# PPMB32-F.net
KiCad netlist of a schematic drawn in EAGLE
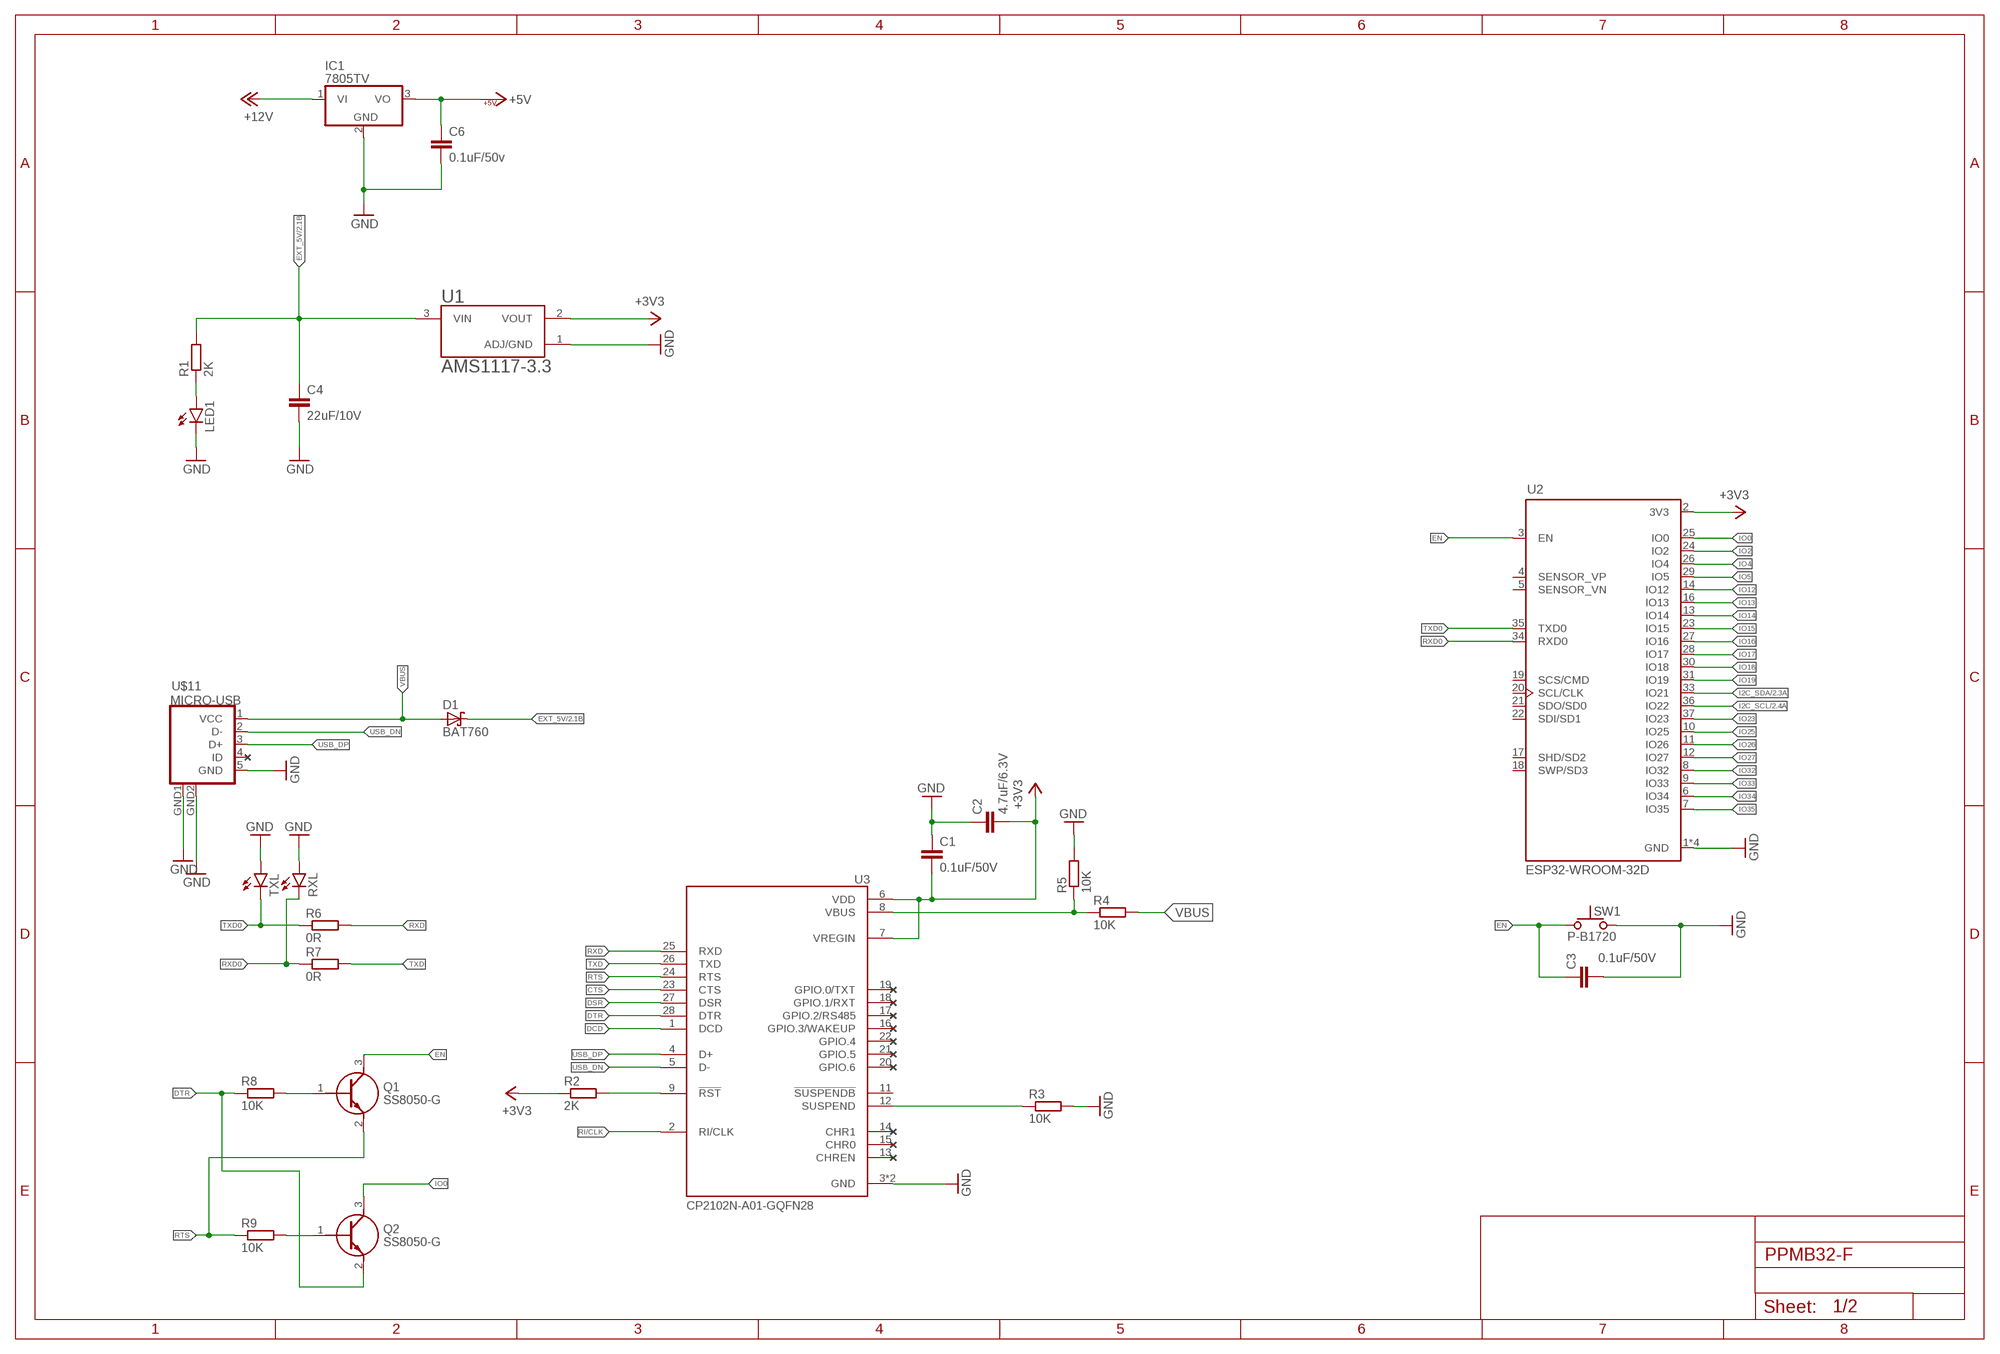
[diagram p0: schematic, sheet 1]
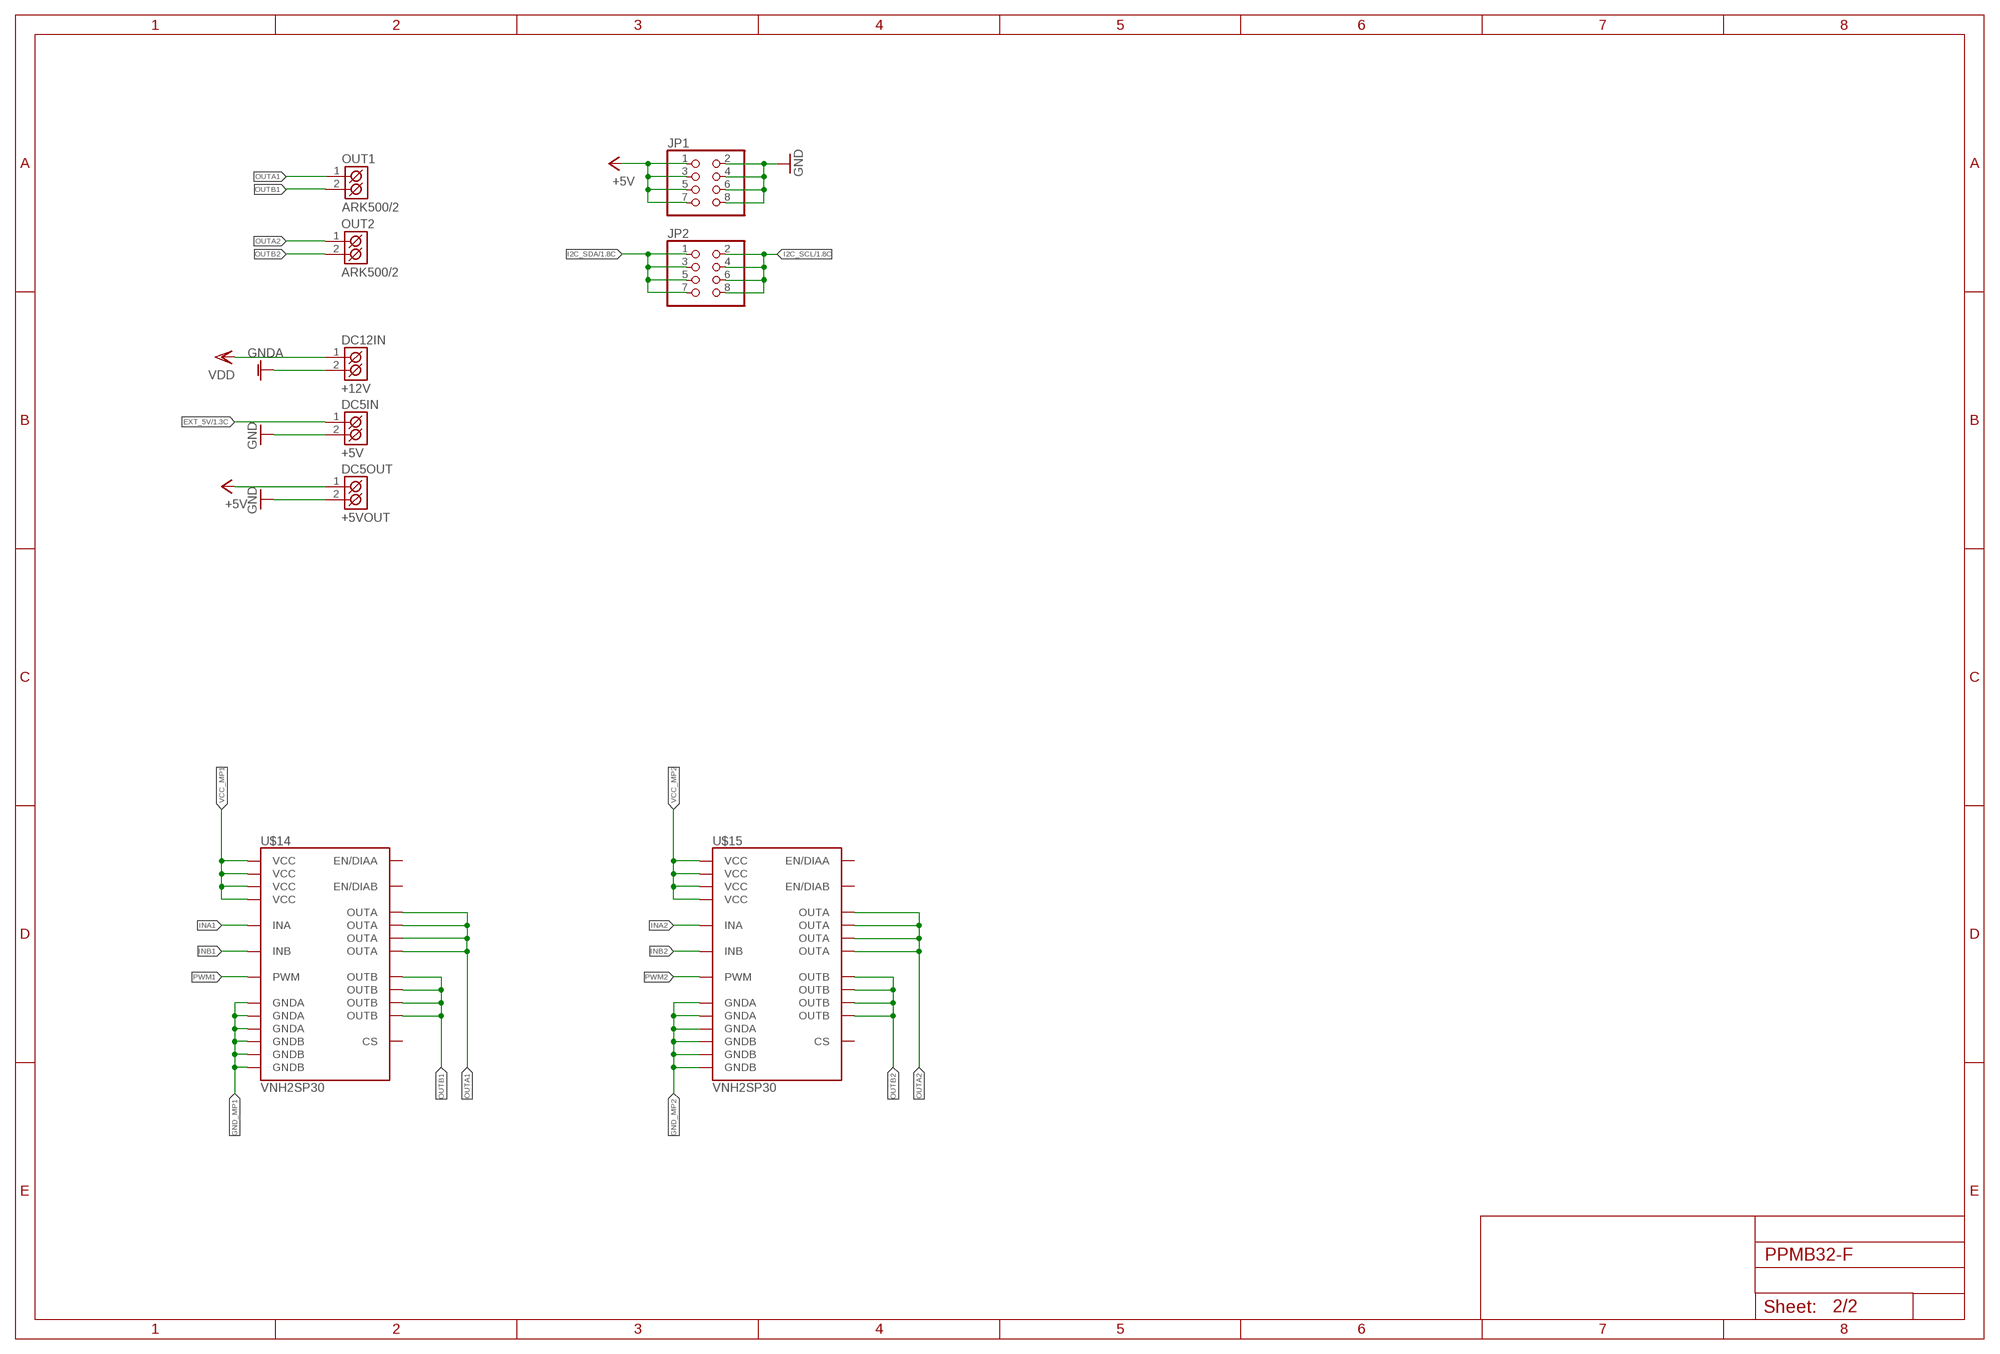
[diagram p1: schematic, sheet 2]

(export (version "E")
  (design (tool "Eeschema 10.0.6"))
  (components
    (comp (ref "C1")
      (value "0.1uF/50V")
      (footprint "eagle-import:C0603")
      (libsource (lib "eagle-import") (part "C-EUC0603"))
    )
    (comp (ref "C2")
      (value "4.7uF/6.3V")
      (footprint "eagle-import:C0603")
      (libsource (lib "eagle-import") (part "C-EUC0603"))
    )
    (comp (ref "C3")
      (value "0.1uF/50V")
      (footprint "eagle-import:C0603")
      (libsource (lib "eagle-import") (part "C-EUC0603"))
    )
    (comp (ref "C4")
      (value "22uF/10V")
      (footprint "eagle-import:C0603")
      (libsource (lib "eagle-import") (part "C-EUC0603"))
    )
    (comp (ref "C6")
      (value "0.1uF/50v")
      (footprint "eagle-import:C0603")
      (libsource (lib "eagle-import") (part "C-EUC0603"))
    )
    (comp (ref "D1")
      (value "BAT760")
      (footprint "eagle-import:SOD323(F)")
      (libsource (lib "eagle-import") (part "BAT760"))
    )
    (comp (ref "IC1")
      (value "7805TV")
      (footprint "eagle-import:TO220V")
      (libsource (lib "eagle-import") (part "78TV05"))
    )
    (comp (ref "LED1")
      (value "LEDCHIP-LED0603")
      (footprint "eagle-import:CHIP-LED0603")
      (libsource (lib "eagle-import") (part "LEDCHIP-LED0603"))
    )
    (comp (ref "Q1")
      (value "SS8050-G")
      (footprint "eagle-import:SOT95P240X115-3N")
      (fields (field (name "MF") "Comchip Technology"))
      (libsource (lib "eagle-import") (part "SS8050-G"))
    )
    (comp (ref "Q2")
      (value "SS8050-G")
      (footprint "eagle-import:SOT95P240X115-3N")
      (fields (field (name "MF") "Comchip Technology"))
      (libsource (lib "eagle-import") (part "SS8050-G"))
    )
    (comp (ref "R1")
      (value "2K")
      (footprint "eagle-import:R0603")
      (libsource (lib "eagle-import") (part "R-EU_R0603"))
    )
    (comp (ref "R2")
      (value "2K")
      (footprint "eagle-import:R0603")
      (libsource (lib "eagle-import") (part "R-EU_R0603"))
    )
    (comp (ref "R3")
      (value "10K")
      (footprint "eagle-import:R0603")
      (libsource (lib "eagle-import") (part "R-EU_R0603"))
    )
    (comp (ref "R4")
      (value "10K")
      (footprint "eagle-import:R0603")
      (libsource (lib "eagle-import") (part "R-EU_R0603"))
    )
    (comp (ref "R5")
      (value "10K")
      (footprint "eagle-import:R0603")
      (libsource (lib "eagle-import") (part "R-EU_R0603"))
    )
    (comp (ref "R6")
      (value "0R")
      (footprint "eagle-import:R0603")
      (libsource (lib "eagle-import") (part "R-EU_R0603"))
    )
    (comp (ref "R7")
      (value "0R")
      (footprint "eagle-import:R0603")
      (libsource (lib "eagle-import") (part "R-EU_R0603"))
    )
    (comp (ref "R8")
      (value "10K")
      (footprint "eagle-import:R0603")
      (libsource (lib "eagle-import") (part "R-EU_R0603"))
    )
    (comp (ref "R9")
      (value "10K")
      (footprint "eagle-import:R0603")
      (libsource (lib "eagle-import") (part "R-EU_R0603"))
    )
    (comp (ref "RXL")
      (value "LEDCHIP-LED0603")
      (footprint "eagle-import:CHIP-LED0603")
      (libsource (lib "eagle-import") (part "LEDCHIP-LED0603"))
    )
    (comp (ref "SW1")
      (value "P-B1720")
      (footprint "eagle-import:P-B1720")
      (libsource (lib "eagle-import") (part "P-B1720"))
    )
    (comp (ref "TXL")
      (value "LEDCHIP-LED0603")
      (footprint "eagle-import:CHIP-LED0603")
      (libsource (lib "eagle-import") (part "LEDCHIP-LED0603"))
    )
    (comp (ref "U$11")
      (value "MICRO-USB")
      (footprint "eagle-import:MICRO-USB")
      (libsource (lib "eagle-import") (part "MICRO-USB"))
    )
    (comp (ref "U1")
      (value "AMS1117-3.3")
      (footprint "eagle-import:SOT229P700X180-4N")
      (fields (field (name "MF") "Advanced Monolithic Systems"))
      (libsource (lib "eagle-import") (part "AMS1117-3.3"))
    )
    (comp (ref "U2")
      (value "ESP32-WROOM-32D")
      (footprint "eagle-import:MODULE_ESP32-WROOM-32D")
      (fields (field (name "MF") "Espressif Systems"))
      (libsource (lib "eagle-import") (part "ESP32-WROOM-32D"))
    )
    (comp (ref "U3")
      (value "CP2102N-A01-GQFN28")
      (footprint "eagle-import:QFN50P500X500X80-29N")
      (fields (field (name "MF") "Silicon Labs"))
      (libsource (lib "eagle-import") (part "CP2102N-A01-GQFN28"))
    )
    (comp (ref "DC5IN")
      (value "+5V")
      (footprint "eagle-import:ARK500_2")
      (libsource (lib "eagle-import") (part "ARK500/2"))
    )
    (comp (ref "DC5OUT")
      (value "+5VOUT")
      (footprint "eagle-import:ARK500_2")
      (libsource (lib "eagle-import") (part "ARK500/2"))
    )
    (comp (ref "DC12IN")
      (value "+12V")
      (footprint "eagle-import:ARK500_2")
      (libsource (lib "eagle-import") (part "ARK500/2"))
    )
    (comp (ref "JP1")
      (value "PINHD-2X4")
      (footprint "eagle-import:2X04")
      (libsource (lib "eagle-import") (part "PINHD-2X4"))
    )
    (comp (ref "JP2")
      (value "PINHD-2X4")
      (footprint "eagle-import:2X04")
      (libsource (lib "eagle-import") (part "PINHD-2X4"))
    )
    (comp (ref "OUT1")
      (value "ARK500/2")
      (footprint "eagle-import:ARK500_2")
      (libsource (lib "eagle-import") (part "ARK500/2"))
    )
    (comp (ref "OUT2")
      (value "ARK500/2")
      (footprint "eagle-import:ARK500_2")
      (libsource (lib "eagle-import") (part "ARK500/2"))
    )
    (comp (ref "U$14")
      (value "VNH2SP30")
      (footprint "eagle-import:VNH2SP30")
      (libsource (lib "eagle-import") (part "VNH2SP30"))
    )
    (comp (ref "U$15")
      (value "VNH2SP30")
      (footprint "eagle-import:VNH2SP30")
      (libsource (lib "eagle-import") (part "VNH2SP30"))
    )
  )
  (nets
    (net (code "1") (name "+3V3") (class "Default")
      (node (ref "C1") (pin "2") (pinfunction "2_2") (pintype "passive"))
      (node (ref "C2") (pin "2") (pinfunction "2_2") (pintype "passive"))
      (node (ref "R2") (pin "1") (pinfunction "1_1") (pintype "passive"))
      (node (ref "U1") (pin "2") (pinfunction "VOUT_2") (pintype "output"))
      (node (ref "U2") (pin "2") (pinfunction "3V3_2") (pintype "power_in"))
      (node (ref "U3") (pin "6") (pinfunction "VDD_6") (pintype "power_in"))
      (node (ref "U3") (pin "7") (pinfunction "VREGIN_7") (pintype "power_in"))
    )
    (net (code "2") (name "+5V") (class "Default")
      (node (ref "C6") (pin "1") (pinfunction "1_1") (pintype "passive"))
      (node (ref "DC5OUT") (pin "1") (pinfunction "K1_1") (pintype "passive"))
      (node (ref "IC1") (pin "3") (pinfunction "VO_3") (pintype "passive"))
      (node (ref "JP1") (pin "1") (pinfunction "1_1") (pintype "passive"))
      (node (ref "JP1") (pin "3") (pinfunction "3_3") (pintype "passive"))
      (node (ref "JP1") (pin "5") (pinfunction "5_5") (pintype "passive"))
      (node (ref "JP1") (pin "7") (pinfunction "7_7") (pintype "passive"))
    )
    (net (code "3") (name "+12V") (class "Default")
      (node (ref "IC1") (pin "1") (pinfunction "VI_1") (pintype "input"))
    )
    (net (code "4") (name "CTS") (class "Default")
      (node (ref "U3") (pin "23") (pinfunction "CTS_23") (pintype "input"))
    )
    (net (code "5") (name "DCD") (class "Default")
      (node (ref "U3") (pin "1") (pinfunction "DCD_1") (pintype "input"))
    )
    (net (code "6") (name "DSR") (class "Default")
      (node (ref "U3") (pin "27") (pinfunction "DSR_27") (pintype "input"))
    )
    (net (code "7") (name "DTR") (class "Default")
      (node (ref "Q2") (pin "2") (pinfunction "E_2") (pintype "bidirectional"))
      (node (ref "R8") (pin "1") (pinfunction "1_1") (pintype "passive"))
      (node (ref "U3") (pin "28") (pinfunction "DTR_28") (pintype "output"))
    )
    (net (code "8") (name "EN") (class "Default")
      (node (ref "C3") (pin "1") (pinfunction "1_1") (pintype "passive"))
      (node (ref "Q1") (pin "3") (pinfunction "C_3") (pintype "bidirectional"))
      (node (ref "SW1") (pin "1") (pinfunction "1_1") (pintype "passive"))
      (node (ref "U2") (pin "3") (pinfunction "EN_3") (pintype "input"))
    )
    (net (code "9") (name "EXT_5V") (class "Default")
      (node (ref "C4") (pin "1") (pinfunction "1_1") (pintype "passive"))
      (node (ref "D1") (pin "1") (pinfunction "K_1") (pintype "passive"))
      (node (ref "DC5IN") (pin "1") (pinfunction "K1_1") (pintype "passive"))
      (node (ref "R1") (pin "2") (pinfunction "2_2") (pintype "passive"))
      (node (ref "U1") (pin "3") (pinfunction "VIN_3") (pintype "input"))
    )
    (net (code "10") (name "GND") (class "Default")
      (node (ref "C1") (pin "1") (pinfunction "1_1") (pintype "passive"))
      (node (ref "C2") (pin "1") (pinfunction "1_1") (pintype "passive"))
      (node (ref "C3") (pin "2") (pinfunction "2_2") (pintype "passive"))
      (node (ref "C4") (pin "2") (pinfunction "2_2") (pintype "passive"))
      (node (ref "C6") (pin "2") (pinfunction "2_2") (pintype "passive"))
      (node (ref "DC5IN") (pin "2") (pinfunction "K2_2") (pintype "passive"))
      (node (ref "DC5OUT") (pin "2") (pinfunction "K2_2") (pintype "passive"))
      (node (ref "IC1") (pin "2") (pinfunction "GND_2") (pintype "passive"))
      (node (ref "JP1") (pin "2") (pinfunction "2_2") (pintype "passive"))
      (node (ref "JP1") (pin "4") (pinfunction "4_4") (pintype "passive"))
      (node (ref "JP1") (pin "6") (pinfunction "6_6") (pintype "passive"))
      (node (ref "JP1") (pin "8") (pinfunction "8_8") (pintype "passive"))
      (node (ref "LED1") (pin "C") (pinfunction "C_C") (pintype "passive"))
      (node (ref "R3") (pin "2") (pinfunction "2_2") (pintype "passive"))
      (node (ref "R5") (pin "2") (pinfunction "2_2") (pintype "passive"))
      (node (ref "RXL") (pin "A") (pinfunction "A_A") (pintype "passive"))
      (node (ref "SW1") (pin "2") (pinfunction "2_2") (pintype "passive"))
      (node (ref "TXL") (pin "A") (pinfunction "A_A") (pintype "passive"))
      (node (ref "U$11") (pin "5") (pinfunction "GND_5") (pintype "power_in"))
      (node (ref "U$11") (pin "GND1") (pinfunction "GND_GND1") (pintype "power_in"))
      (node (ref "U$11") (pin "GND2") (pinfunction "GND_GND2") (pintype "power_in"))
      (node (ref "U1") (pin "1") (pinfunction "ADJ/GND_1") (pintype "power_in"))
      (node (ref "U2") (pin "1") (pinfunction "GND_1") (pintype "power_in"))
      (node (ref "U2") (pin "15") (pinfunction "GND_15") (pintype "power_in"))
      (node (ref "U2") (pin "38") (pinfunction "GND_38") (pintype "power_in"))
      (node (ref "U2") (pin "39") (pinfunction "GND_39") (pintype "power_in"))
      (node (ref "U3") (pin "29") (pinfunction "GND_29") (pintype "power_in"))
      (node (ref "U3") (pin "3") (pinfunction "GND_3") (pintype "power_in"))
    )
    (net (code "11") (name "GNDA") (class "Default")
      (node (ref "DC12IN") (pin "2") (pinfunction "K2_2") (pintype "passive"))
    )
    (net (code "12") (name "GND_MP1") (class "Default")
      (node (ref "U$14") (pin "18") (pinfunction "GNDB_18") (pintype "bidirectional"))
      (node (ref "U$14") (pin "19") (pinfunction "GNDB_19") (pintype "bidirectional"))
      (node (ref "U$14") (pin "20") (pinfunction "GNDB_20") (pintype "bidirectional"))
      (node (ref "U$14") (pin "26") (pinfunction "GNDA_26") (pintype "bidirectional"))
      (node (ref "U$14") (pin "27") (pinfunction "GNDA_27") (pintype "bidirectional"))
      (node (ref "U$14") (pin "28") (pinfunction "GNDA_28") (pintype "bidirectional"))
    )
    (net (code "13") (name "GND_MP2") (class "Default")
      (node (ref "U$15") (pin "18") (pinfunction "GNDB_18") (pintype "bidirectional"))
      (node (ref "U$15") (pin "19") (pinfunction "GNDB_19") (pintype "bidirectional"))
      (node (ref "U$15") (pin "20") (pinfunction "GNDB_20") (pintype "bidirectional"))
      (node (ref "U$15") (pin "26") (pinfunction "GNDA_26") (pintype "bidirectional"))
      (node (ref "U$15") (pin "27") (pinfunction "GNDA_27") (pintype "bidirectional"))
      (node (ref "U$15") (pin "28") (pinfunction "GNDA_28") (pintype "bidirectional"))
    )
    (net (code "14") (name "I2C_SCL") (class "Default")
      (node (ref "JP2") (pin "2") (pinfunction "2_2") (pintype "passive"))
      (node (ref "JP2") (pin "4") (pinfunction "4_4") (pintype "passive"))
      (node (ref "JP2") (pin "6") (pinfunction "6_6") (pintype "passive"))
      (node (ref "JP2") (pin "8") (pinfunction "8_8") (pintype "passive"))
      (node (ref "U2") (pin "36") (pinfunction "IO22_36") (pintype "bidirectional"))
    )
    (net (code "15") (name "I2C_SDA") (class "Default")
      (node (ref "JP2") (pin "1") (pinfunction "1_1") (pintype "passive"))
      (node (ref "JP2") (pin "3") (pinfunction "3_3") (pintype "passive"))
      (node (ref "JP2") (pin "5") (pinfunction "5_5") (pintype "passive"))
      (node (ref "JP2") (pin "7") (pinfunction "7_7") (pintype "passive"))
      (node (ref "U2") (pin "33") (pinfunction "IO21_33") (pintype "bidirectional"))
    )
    (net (code "16") (name "INA1") (class "Default")
      (node (ref "U$14") (pin "5") (pinfunction "INA_5") (pintype "bidirectional"))
    )
    (net (code "17") (name "INA2") (class "Default")
      (node (ref "U$15") (pin "5") (pinfunction "INA_5") (pintype "bidirectional"))
    )
    (net (code "18") (name "INB1") (class "Default")
      (node (ref "U$14") (pin "11") (pinfunction "INB_11") (pintype "bidirectional"))
    )
    (net (code "19") (name "INB2") (class "Default")
      (node (ref "U$15") (pin "11") (pinfunction "INB_11") (pintype "bidirectional"))
    )
    (net (code "20") (name "IO0") (class "Default")
      (node (ref "Q2") (pin "3") (pinfunction "C_3") (pintype "bidirectional"))
      (node (ref "U2") (pin "25") (pinfunction "IO0_25") (pintype "bidirectional"))
    )
    (net (code "21") (name "IO2") (class "Default")
      (node (ref "U2") (pin "24") (pinfunction "IO2_24") (pintype "bidirectional"))
    )
    (net (code "22") (name "IO4") (class "Default")
      (node (ref "U2") (pin "26") (pinfunction "IO4_26") (pintype "bidirectional"))
    )
    (net (code "23") (name "IO5") (class "Default")
      (node (ref "U2") (pin "29") (pinfunction "IO5_29") (pintype "bidirectional"))
    )
    (net (code "24") (name "IO12") (class "Default")
      (node (ref "U2") (pin "14") (pinfunction "IO12_14") (pintype "bidirectional"))
    )
    (net (code "25") (name "IO13") (class "Default")
      (node (ref "U2") (pin "16") (pinfunction "IO13_16") (pintype "bidirectional"))
    )
    (net (code "26") (name "IO14") (class "Default")
      (node (ref "U2") (pin "13") (pinfunction "IO14_13") (pintype "bidirectional"))
    )
    (net (code "27") (name "IO15") (class "Default")
      (node (ref "U2") (pin "23") (pinfunction "IO15_23") (pintype "bidirectional"))
    )
    (net (code "28") (name "IO16") (class "Default")
      (node (ref "U2") (pin "27") (pinfunction "IO16_27") (pintype "bidirectional"))
    )
    (net (code "29") (name "IO17") (class "Default")
      (node (ref "U2") (pin "28") (pinfunction "IO17_28") (pintype "bidirectional"))
    )
    (net (code "30") (name "IO18") (class "Default")
      (node (ref "U2") (pin "30") (pinfunction "IO18_30") (pintype "bidirectional"))
    )
    (net (code "31") (name "IO19") (class "Default")
      (node (ref "U2") (pin "31") (pinfunction "IO19_31") (pintype "bidirectional"))
    )
    (net (code "32") (name "IO23") (class "Default")
      (node (ref "U2") (pin "37") (pinfunction "IO23_37") (pintype "bidirectional"))
    )
    (net (code "33") (name "IO25") (class "Default")
      (node (ref "U2") (pin "10") (pinfunction "IO25_10") (pintype "bidirectional"))
    )
    (net (code "34") (name "IO26") (class "Default")
      (node (ref "U2") (pin "11") (pinfunction "IO26_11") (pintype "bidirectional"))
    )
    (net (code "35") (name "IO27") (class "Default")
      (node (ref "U2") (pin "12") (pinfunction "IO27_12") (pintype "bidirectional"))
    )
    (net (code "36") (name "IO32") (class "Default")
      (node (ref "U2") (pin "8") (pinfunction "IO32_8") (pintype "bidirectional"))
    )
    (net (code "37") (name "IO33") (class "Default")
      (node (ref "U2") (pin "9") (pinfunction "IO33_9") (pintype "bidirectional"))
    )
    (net (code "38") (name "IO34") (class "Default")
      (node (ref "U2") (pin "6") (pinfunction "IO34_6") (pintype "bidirectional"))
    )
    (net (code "39") (name "IO35") (class "Default")
      (node (ref "U2") (pin "7") (pinfunction "IO35_7") (pintype "bidirectional"))
    )
    (net (code "40") (name "Net-(LED1-PadA)") (class "Default")
      (node (ref "LED1") (pin "A") (pinfunction "A_A") (pintype "passive"))
      (node (ref "R1") (pin "1") (pinfunction "1_1") (pintype "passive"))
    )
    (net (code "41") (name "Net-(Q1-B)") (class "Default")
      (node (ref "Q1") (pin "1") (pinfunction "B_1") (pintype "bidirectional"))
      (node (ref "R8") (pin "2") (pinfunction "2_2") (pintype "passive"))
    )
    (net (code "42") (name "Net-(Q2-B)") (class "Default")
      (node (ref "Q2") (pin "1") (pinfunction "B_1") (pintype "bidirectional"))
      (node (ref "R9") (pin "2") (pinfunction "2_2") (pintype "passive"))
    )
    (net (code "43") (name "Net-(U3-SUSPEND)") (class "Default")
      (node (ref "R3") (pin "1") (pinfunction "1_1") (pintype "passive"))
      (node (ref "U3") (pin "12") (pinfunction "SUSPEND_12") (pintype "output"))
    )
    (net (code "44") (name "Net-(U3-VBUS)") (class "Default")
      (node (ref "R4") (pin "1") (pinfunction "1_1") (pintype "passive"))
      (node (ref "R5") (pin "1") (pinfunction "1_1") (pintype "passive"))
      (node (ref "U3") (pin "8") (pinfunction "VBUS_8") (pintype "power_in"))
    )
    (net (code "45") (name "Net-(U3-~{RST})") (class "Default")
      (node (ref "R2") (pin "2") (pinfunction "2_2") (pintype "passive"))
      (node (ref "U3") (pin "9") (pinfunction "~{RST}_9") (pintype "input"))
    )
    (net (code "46") (name "OUTA1") (class "Default")
      (node (ref "OUT1") (pin "1") (pinfunction "K1_1") (pintype "passive"))
      (node (ref "U$14") (pin "1") (pinfunction "OUTA_1") (pintype "bidirectional"))
      (node (ref "U$14") (pin "25") (pinfunction "OUTA_25") (pintype "bidirectional"))
      (node (ref "U$14") (pin "30") (pinfunction "OUTA_30") (pintype "bidirectional"))
      (node (ref "U$14") (pin "SLUG3") (pinfunction "OUTA_SLUG3") (pintype "bidirectional"))
    )
    (net (code "47") (name "OUTA2") (class "Default")
      (node (ref "OUT2") (pin "1") (pinfunction "K1_1") (pintype "passive"))
      (node (ref "U$15") (pin "1") (pinfunction "OUTA_1") (pintype "bidirectional"))
      (node (ref "U$15") (pin "25") (pinfunction "OUTA_25") (pintype "bidirectional"))
      (node (ref "U$15") (pin "30") (pinfunction "OUTA_30") (pintype "bidirectional"))
      (node (ref "U$15") (pin "SLUG3") (pinfunction "OUTA_SLUG3") (pintype "bidirectional"))
    )
    (net (code "48") (name "OUTB1") (class "Default")
      (node (ref "OUT1") (pin "2") (pinfunction "K2_2") (pintype "passive"))
      (node (ref "U$14") (pin "15") (pinfunction "OUTB_15") (pintype "bidirectional"))
      (node (ref "U$14") (pin "16") (pinfunction "OUTB_16") (pintype "bidirectional"))
      (node (ref "U$14") (pin "21") (pinfunction "OUTB_21") (pintype "bidirectional"))
      (node (ref "U$14") (pin "SLUG2") (pinfunction "OUTB_SLUG2") (pintype "bidirectional"))
    )
    (net (code "49") (name "OUTB2") (class "Default")
      (node (ref "OUT2") (pin "2") (pinfunction "K2_2") (pintype "passive"))
      (node (ref "U$15") (pin "15") (pinfunction "OUTB_15") (pintype "bidirectional"))
      (node (ref "U$15") (pin "16") (pinfunction "OUTB_16") (pintype "bidirectional"))
      (node (ref "U$15") (pin "21") (pinfunction "OUTB_21") (pintype "bidirectional"))
      (node (ref "U$15") (pin "SLUG2") (pinfunction "OUTB_SLUG2") (pintype "bidirectional"))
    )
    (net (code "50") (name "PWM1") (class "Default")
      (node (ref "U$14") (pin "8") (pinfunction "PWM_8") (pintype "bidirectional"))
    )
    (net (code "51") (name "PWM2") (class "Default")
      (node (ref "U$15") (pin "8") (pinfunction "PWM_8") (pintype "bidirectional"))
    )
    (net (code "52") (name "RI{slash}CLK") (class "Default")
      (node (ref "U3") (pin "2") (pinfunction "RI/CLK_2") (pintype "bidirectional"))
    )
    (net (code "53") (name "RTS") (class "Default")
      (node (ref "Q1") (pin "2") (pinfunction "E_2") (pintype "bidirectional"))
      (node (ref "R9") (pin "1") (pinfunction "1_1") (pintype "passive"))
      (node (ref "U3") (pin "24") (pinfunction "RTS_24") (pintype "output"))
    )
    (net (code "54") (name "RXD") (class "Default")
      (node (ref "R6") (pin "2") (pinfunction "2_2") (pintype "passive"))
      (node (ref "U3") (pin "25") (pinfunction "RXD_25") (pintype "input"))
    )
    (net (code "55") (name "RXD0") (class "Default")
      (node (ref "R7") (pin "1") (pinfunction "1_1") (pintype "passive"))
      (node (ref "RXL") (pin "C") (pinfunction "C_C") (pintype "passive"))
      (node (ref "U2") (pin "34") (pinfunction "RXD0_34") (pintype "bidirectional"))
    )
    (net (code "56") (name "TXD") (class "Default")
      (node (ref "R7") (pin "2") (pinfunction "2_2") (pintype "passive"))
      (node (ref "U3") (pin "26") (pinfunction "TXD_26") (pintype "output"))
    )
    (net (code "57") (name "TXD0") (class "Default")
      (node (ref "R6") (pin "1") (pinfunction "1_1") (pintype "passive"))
      (node (ref "TXL") (pin "C") (pinfunction "C_C") (pintype "passive"))
      (node (ref "U2") (pin "35") (pinfunction "TXD0_35") (pintype "bidirectional"))
    )
    (net (code "58") (name "USB_DN") (class "Default")
      (node (ref "U$11") (pin "2") (pinfunction "D-_2") (pintype "bidirectional"))
      (node (ref "U3") (pin "5") (pinfunction "D-_5") (pintype "bidirectional"))
    )
    (net (code "59") (name "USB_DP") (class "Default")
      (node (ref "U$11") (pin "3") (pinfunction "D+_3") (pintype "bidirectional"))
      (node (ref "U3") (pin "4") (pinfunction "D+_4") (pintype "bidirectional"))
    )
    (net (code "60") (name "VBUS") (class "Default")
      (node (ref "D1") (pin "2") (pinfunction "A_2") (pintype "passive"))
      (node (ref "R4") (pin "2") (pinfunction "2_2") (pintype "passive"))
      (node (ref "U$11") (pin "1") (pinfunction "VCC_1") (pintype "power_in"))
    )
    (net (code "61") (name "VCC_MP1") (class "Default")
      (node (ref "U$14") (pin "13") (pinfunction "VCC_13") (pintype "bidirectional"))
      (node (ref "U$14") (pin "23") (pinfunction "VCC_23") (pintype "bidirectional"))
      (node (ref "U$14") (pin "3") (pinfunction "VCC_3") (pintype "bidirectional"))
      (node (ref "U$14") (pin "SLUG1") (pinfunction "VCC_SLUG1") (pintype "bidirectional"))
    )
    (net (code "62") (name "VCC_MP2") (class "Default")
      (node (ref "U$15") (pin "13") (pinfunction "VCC_13") (pintype "bidirectional"))
      (node (ref "U$15") (pin "23") (pinfunction "VCC_23") (pintype "bidirectional"))
      (node (ref "U$15") (pin "3") (pinfunction "VCC_3") (pintype "bidirectional"))
      (node (ref "U$15") (pin "SLUG1") (pinfunction "VCC_SLUG1") (pintype "bidirectional"))
    )
    (net (code "63") (name "VDD") (class "Default")
      (node (ref "DC12IN") (pin "1") (pinfunction "K1_1") (pintype "passive"))
    )
    (net (code "64") (name "unconnected-(SW1-Pad3)") (class "Default")
      (node (ref "SW1") (pin "3") (pinfunction "3_3") (pintype "passive"))
    )
    (net (code "65") (name "unconnected-(SW1-Pad4)") (class "Default")
      (node (ref "SW1") (pin "4") (pinfunction "4_4") (pintype "passive"))
    )
    (net (code "66") (name "unconnected-(U$11-ID-Pad4)") (class "Default")
      (node (ref "U$11") (pin "4") (pinfunction "ID_4") (pintype "bidirectional"))
    )
    (net (code "67") (name "unconnected-(U$14-CS-Pad9)") (class "Default")
      (node (ref "U$14") (pin "9") (pinfunction "CS_9") (pintype "bidirectional"))
    )
    (net (code "68") (name "unconnected-(U$14-EN{slash}DIAA-Pad6)") (class "Default")
      (node (ref "U$14") (pin "6") (pinfunction "EN/DIAA_6") (pintype "bidirectional"))
    )
    (net (code "69") (name "unconnected-(U$14-EN{slash}DIAB-Pad10)") (class "Default")
      (node (ref "U$14") (pin "10") (pinfunction "EN/DIAB_10") (pintype "bidirectional"))
    )
    (net (code "70") (name "unconnected-(U$15-CS-Pad9)") (class "Default")
      (node (ref "U$15") (pin "9") (pinfunction "CS_9") (pintype "bidirectional"))
    )
    (net (code "71") (name "unconnected-(U$15-EN{slash}DIAA-Pad6)") (class "Default")
      (node (ref "U$15") (pin "6") (pinfunction "EN/DIAA_6") (pintype "bidirectional"))
    )
    (net (code "72") (name "unconnected-(U$15-EN{slash}DIAB-Pad10)") (class "Default")
      (node (ref "U$15") (pin "10") (pinfunction "EN/DIAB_10") (pintype "bidirectional"))
    )
    (net (code "73") (name "unconnected-(U2-SCL{slash}CLK-Pad20)") (class "Default")
      (node (ref "U2") (pin "20") (pinfunction "SCL/CLK_20") (pintype "bidirectional"))
    )
    (net (code "74") (name "unconnected-(U2-SCS{slash}CMD-Pad19)") (class "Default")
      (node (ref "U2") (pin "19") (pinfunction "SCS/CMD_19") (pintype "bidirectional"))
    )
    (net (code "75") (name "unconnected-(U2-SDI{slash}SD1-Pad22)") (class "Default")
      (node (ref "U2") (pin "22") (pinfunction "SDI/SD1_22") (pintype "bidirectional"))
    )
    (net (code "76") (name "unconnected-(U2-SDO{slash}SD0-Pad21)") (class "Default")
      (node (ref "U2") (pin "21") (pinfunction "SDO/SD0_21") (pintype "bidirectional"))
    )
    (net (code "77") (name "unconnected-(U2-SENSOR_VN-Pad5)") (class "Default")
      (node (ref "U2") (pin "5") (pinfunction "SENSOR_VN_5") (pintype "input"))
    )
    (net (code "78") (name "unconnected-(U2-SENSOR_VP-Pad4)") (class "Default")
      (node (ref "U2") (pin "4") (pinfunction "SENSOR_VP_4") (pintype "input"))
    )
    (net (code "79") (name "unconnected-(U2-SHD{slash}SD2-Pad17)") (class "Default")
      (node (ref "U2") (pin "17") (pinfunction "SHD/SD2_17") (pintype "bidirectional"))
    )
    (net (code "80") (name "unconnected-(U2-SWP{slash}SD3-Pad18)") (class "Default")
      (node (ref "U2") (pin "18") (pinfunction "SWP/SD3_18") (pintype "bidirectional"))
    )
    (net (code "81") (name "unconnected-(U3-CHR0-Pad15)") (class "Default")
      (node (ref "U3") (pin "15") (pinfunction "CHR0_15") (pintype "output"))
    )
    (net (code "82") (name "unconnected-(U3-CHR1-Pad14)") (class "Default")
      (node (ref "U3") (pin "14") (pinfunction "CHR1_14") (pintype "output"))
    )
    (net (code "83") (name "unconnected-(U3-CHREN-Pad13)") (class "Default")
      (node (ref "U3") (pin "13") (pinfunction "CHREN_13") (pintype "output"))
    )
    (net (code "84") (name "unconnected-(U3-GPIO.0{slash}TXT-Pad19)") (class "Default")
      (node (ref "U3") (pin "19") (pinfunction "GPIO.0/TXT_19") (pintype "bidirectional"))
    )
    (net (code "85") (name "unconnected-(U3-GPIO.1{slash}RXT-Pad18)") (class "Default")
      (node (ref "U3") (pin "18") (pinfunction "GPIO.1/RXT_18") (pintype "bidirectional"))
    )
    (net (code "86") (name "unconnected-(U3-GPIO.2{slash}RS485-Pad17)") (class "Default")
      (node (ref "U3") (pin "17") (pinfunction "GPIO.2/RS485_17") (pintype "bidirectional"))
    )
    (net (code "87") (name "unconnected-(U3-GPIO.3{slash}WAKEUP-Pad16)") (class "Default")
      (node (ref "U3") (pin "16") (pinfunction "GPIO.3/WAKEUP_16") (pintype "bidirectional"))
    )
    (net (code "88") (name "unconnected-(U3-GPIO.4-Pad22)") (class "Default")
      (node (ref "U3") (pin "22") (pinfunction "GPIO.4_22") (pintype "bidirectional"))
    )
    (net (code "89") (name "unconnected-(U3-GPIO.5-Pad21)") (class "Default")
      (node (ref "U3") (pin "21") (pinfunction "GPIO.5_21") (pintype "bidirectional"))
    )
    (net (code "90") (name "unconnected-(U3-GPIO.6-Pad20)") (class "Default")
      (node (ref "U3") (pin "20") (pinfunction "GPIO.6_20") (pintype "bidirectional"))
    )
    (net (code "91") (name "unconnected-(U3-~{SUSPENDB}-Pad11)") (class "Default")
      (node (ref "U3") (pin "11") (pinfunction "~{SUSPENDB}_11") (pintype "output"))
    )
  )
)
